# STM32_microcontroller_power.net
KiCad netlist of a schematic drawn in Altium Designer
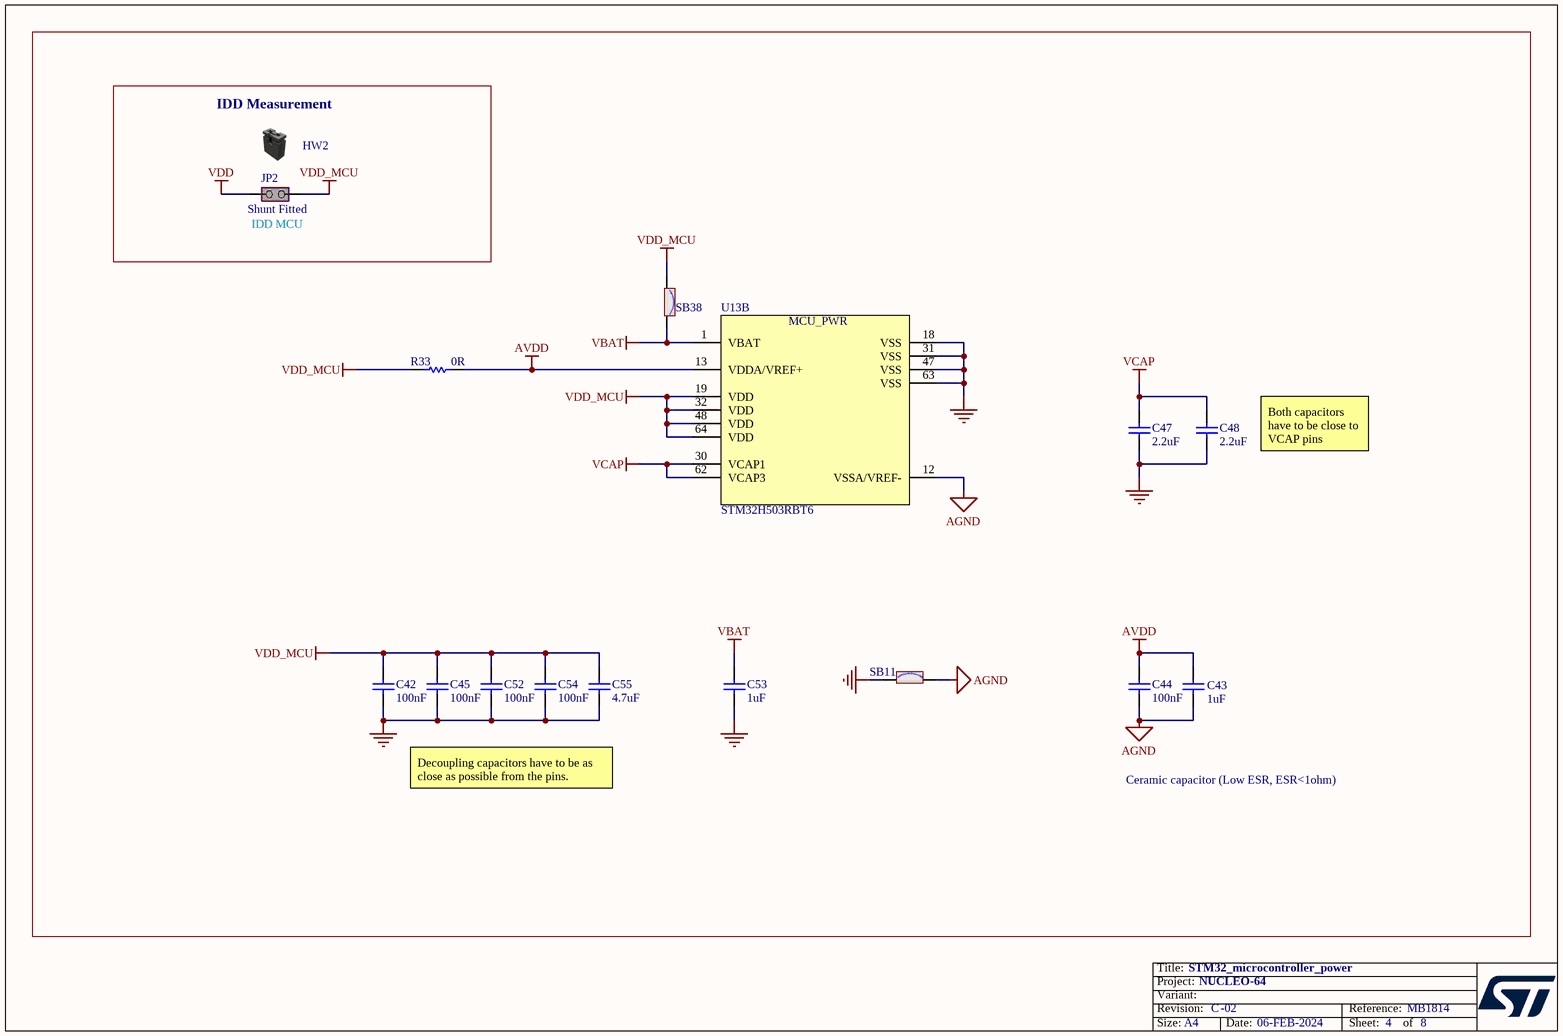
[diagram p0: STM32_microcontroller_power.SchDoc]

(export (version "E")
  (design (tool "Eeschema 10.0.6"))
  (components
    (comp (ref "C42")
      (value "100nF")
      (footprint "C0402")
      (description "Capacitor, MLCC, 100nF, 16V, X7R, +/-10%, 0402, T=0.5mm")
      (fields (field (name "INTERNAL_PART_NUMBER") "MCD-00006") (field (name "MANUFACTURER") "YAGEO"))
      (libsource (lib "MCD_PARTS_database") (part "Capacitor"))
    )
    (comp (ref "C43")
      (value "1uF")
      (footprint "C0603")
      (description "Capacitor, MLCC, 1uF, 16V, X5R, 10%, 0603, T=0,8mm")
      (fields
        (field (name "INTERNAL_PART_NUMBER") "MCD-00010")
        (field (name "MANUFACTURER_PART_NUMBER") "CC0603KRX5R7BB105")
        (field (name "PROVIDED_BY") "Subcon")
      )
      (libsource (lib "MCD_PARTS_database") (part "Capacitor"))
    )
    (comp (ref "C44")
      (value "100nF")
      (footprint "C0402")
      (description "Capacitor, MLCC, 100nF, 16V, X7R, +/-10%, 0402, T=0.5mm")
      (fields (field (name "INTERNAL_PART_NUMBER") "MCD-00006") (field (name "MANUFACTURER") "YAGEO"))
      (libsource (lib "MCD_PARTS_database") (part "Capacitor"))
    )
    (comp (ref "C45")
      (value "100nF")
      (footprint "C0402")
      (description "Capacitor, MLCC, 100nF, 16V, X7R, +/-10%, 0402, T=0.5mm")
      (fields (field (name "INTERNAL_PART_NUMBER") "MCD-00006") (field (name "MANUFACTURER") "YAGEO"))
      (libsource (lib "MCD_PARTS_database") (part "Capacitor"))
    )
    (comp (ref "C47")
      (value "2.2uF")
      (footprint "C0603")
      (description "Capacitor, MLCC, 2.2uF, 10V, X5R, +/- 10%, 0603, T=0,8mm")
      (fields (field (name "INTERNAL_PART_NUMBER") "MCD-00012") (field (name "BMS_PART_NUMBER") "9142010"))
      (libsource (lib "MCD_PARTS_database") (part "Capacitor"))
    )
    (comp (ref "C48")
      (value "2.2uF")
      (footprint "C0603")
      (description "Capacitor, MLCC, 2.2uF, 10V, X5R, +/- 10%, 0603, T=0,8mm")
      (fields (field (name "INTERNAL_PART_NUMBER") "MCD-00012") (field (name "BMS_PART_NUMBER") "9142010"))
      (libsource (lib "MCD_PARTS_database") (part "Capacitor"))
    )
    (comp (ref "C52")
      (value "100nF")
      (footprint "C0402")
      (description "Capacitor, MLCC, 100nF, 16V, X7R, +/-10%, 0402, T=0.5mm")
      (fields (field (name "INTERNAL_PART_NUMBER") "MCD-00006") (field (name "MANUFACTURER") "YAGEO"))
      (libsource (lib "MCD_PARTS_database") (part "Capacitor"))
    )
    (comp (ref "C53")
      (value "1uF")
      (footprint "C0603")
      (description "Capacitor, MLCC, 1uF, 16V, X5R, 10%, 0603, T=0,8mm")
      (fields
        (field (name "INTERNAL_PART_NUMBER") "MCD-00010")
        (field (name "MANUFACTURER_PART_NUMBER") "CC0603KRX5R7BB105")
        (field (name "PROVIDED_BY") "Subcon")
      )
      (libsource (lib "MCD_PARTS_database") (part "Capacitor"))
    )
    (comp (ref "C54")
      (value "100nF")
      (footprint "C0402")
      (description "Capacitor, MLCC, 100nF, 16V, X7R, +/-10%, 0402, T=0.5mm")
      (fields (field (name "INTERNAL_PART_NUMBER") "MCD-00006") (field (name "MANUFACTURER") "YAGEO"))
      (libsource (lib "MCD_PARTS_database") (part "Capacitor"))
    )
    (comp (ref "C55")
      (value "4.7uF")
      (footprint "C0603")
      (description "Capacitor, MLCC, 4.7uF, 16V, X5R, 10%, 0603, T=0.8mm")
      (fields
        (field (name "INTERNAL_PART_NUMBER") "MCD-00009")
        (field (name "MANUFACTURER_PART_NUMBER") "CC0603KRX5R7BB475")
        (field (name "PROVIDED_BY") "subcon")
      )
      (libsource (lib "MCD_PARTS_database") (part "Capacitor"))
    )
    (comp (ref "HW2")
      (value "~")
      (description "SHUNT 2.54mm BLACK")
      (fields
        (field (name "INTERNAL_PART_NUMBER") "MCD-00043")
        (field (name "MANUFACTURER_PART_NUMBER") "SNT-100-BK-G")
        (field (name "PROVIDED_BY") "Subcon")
      )
      (libsource (lib "MCD_PARTS_database") (part "Shunt Black 2.54mm"))
    )
    (comp (ref "JP2")
      (value "Shunt Fitted")
      (footprint "CON_SAMTEC_TSW-102-07-G-S")
      (description "Header, 2x1, 2,54mm, VR, TH, Height 5.84mm/2.54mm - Shunt Fitted by default")
      (fields
        (field (name "INTERNAL_PART_NUMBER") "MCD-00683")
        (field (name "MANUFACTURER_PART_NUMBER") "TSW-102-07-x-S")
        (field (name "PROVIDED_BY") "Subcon")
      )
      (libsource (lib "MCD_PARTS_database") (part "Jumper_Header 2x1 Fitted"))
    )
    (comp (ref "R33")
      (value "0R")
      (footprint "R0603")
      (description "Resistor, 0R, 0603, +/-5%, 1/10W")
      (fields (field (name "INTERNAL_PART_NUMBER") "MCD-00056") (field (name "MANUFACTURER") "YAGEO"))
      (libsource (lib "MCD_PARTS_database") (part "Resistor"))
    )
    (comp (ref "SB11")
      (value "~")
      (footprint "SOLDER-BRIDGE_R0603-0R")
      (description "Solder Bridge ON")
      (fields
        (field (name "INTERNAL_PART_NUMBER") "MCD-00071")
        (field (name "MANUFACTURER_PART_NUMBER") "RC0603JR-070RL")
        (field (name "PROVIDED_BY") "SUBCO")
      )
      (libsource (lib "") (part "SB_ON_1"))
    )
    (comp (ref "SB38")
      (value "~")
      (footprint "SOLDER-BRIDGE_R0603-0R")
      (description "Solder Bridge ON")
      (fields
        (field (name "INTERNAL_PART_NUMBER") "MCD-00071")
        (field (name "MANUFACTURER_PART_NUMBER") "RC0603JR-070RL")
        (field (name "PROVIDED_BY") "SUBCO")
      )
      (libsource (lib "MCD_PARTS_database") (part "SB_ON"))
    )
    (comp (ref "U13")
      (value "STM32H503RBT6")
      (footprint "ICC_LQFP64_10X10_P050_SOCKET_YAMAICHI_IC149-064-069-B5_NM")
      (description "MCU, Arm Cortex-M33, 250MHz, 32-bit MCU, 128KB flash, 32KB SRAM")
      (fields
        (field (name "INTERNAL_PART_NUMBER") "MCD-02438")
        (field (name "MANUFACTURER") "STMICROELECTRONICS")
      )
      (libsource (lib "MCD_PARTS_database") (part "STM32H503RBH6"))
    )
  )
  (nets
    (net (code "1") (name "AGND") (class "Default")
      (node (ref "C43") (pin "1") (pinfunction "1_1") (pintype "passive"))
      (node (ref "C44") (pin "1") (pinfunction "1_1") (pintype "passive"))
      (node (ref "SB11") (pin "2") (pinfunction "2_2") (pintype "passive"))
      (node (ref "U13") (pin "12") (pinfunction "VSSA/VREF-_12") (pintype "passive"))
    )
    (net (code "2") (name "AVDD") (class "Default")
      (node (ref "C43") (pin "2") (pinfunction "2_2") (pintype "passive"))
      (node (ref "C44") (pin "2") (pinfunction "2_2") (pintype "passive"))
      (node (ref "R33") (pin "2") (pinfunction "2_2") (pintype "passive"))
      (node (ref "U13") (pin "13") (pinfunction "VDDA/VREF+_13") (pintype "passive"))
    )
    (net (code "3") (name "GND") (class "Default")
      (node (ref "C42") (pin "1") (pinfunction "1_1") (pintype "passive"))
      (node (ref "C45") (pin "1") (pinfunction "1_1") (pintype "passive"))
      (node (ref "C47") (pin "1") (pinfunction "1_1") (pintype "passive"))
      (node (ref "C48") (pin "1") (pinfunction "1_1") (pintype "passive"))
      (node (ref "C52") (pin "1") (pinfunction "1_1") (pintype "passive"))
      (node (ref "C53") (pin "1") (pinfunction "1_1") (pintype "passive"))
      (node (ref "C54") (pin "1") (pinfunction "1_1") (pintype "passive"))
      (node (ref "C55") (pin "1") (pinfunction "1_1") (pintype "passive"))
      (node (ref "SB11") (pin "1") (pinfunction "1_1") (pintype "passive"))
      (node (ref "U13") (pin "18") (pinfunction "VSS_18") (pintype "passive"))
      (node (ref "U13") (pin "31") (pinfunction "VSS_31") (pintype "passive"))
      (node (ref "U13") (pin "47") (pinfunction "VSS_47") (pintype "passive"))
      (node (ref "U13") (pin "63") (pinfunction "VSS_63") (pintype "passive"))
    )
    (net (code "4") (name "VBAT") (class "Default")
      (node (ref "C53") (pin "2") (pinfunction "2_2") (pintype "passive"))
      (node (ref "SB38") (pin "2") (pinfunction "2_2") (pintype "passive"))
      (node (ref "U13") (pin "1") (pinfunction "VBAT_1") (pintype "passive"))
    )
    (net (code "5") (name "VCAP") (class "Default")
      (node (ref "C47") (pin "2") (pinfunction "2_2") (pintype "passive"))
      (node (ref "C48") (pin "2") (pinfunction "2_2") (pintype "passive"))
      (node (ref "U13") (pin "30") (pinfunction "VCAP1_30") (pintype "passive"))
      (node (ref "U13") (pin "62") (pinfunction "VCAP3_62") (pintype "passive"))
    )
    (net (code "6") (name "VDD") (class "Default")
      (node (ref "JP2") (pin "1") (pinfunction "COMMON_1") (pintype "passive"))
    )
    (net (code "7") (name "VDD_MCU") (class "Default")
      (node (ref "C42") (pin "2") (pinfunction "2_2") (pintype "passive"))
      (node (ref "C45") (pin "2") (pinfunction "2_2") (pintype "passive"))
      (node (ref "C52") (pin "2") (pinfunction "2_2") (pintype "passive"))
      (node (ref "C54") (pin "2") (pinfunction "2_2") (pintype "passive"))
      (node (ref "C55") (pin "2") (pinfunction "2_2") (pintype "passive"))
      (node (ref "JP2") (pin "2") (pinfunction "NO_2") (pintype "passive"))
      (node (ref "R33") (pin "1") (pinfunction "1_1") (pintype "passive"))
      (node (ref "SB38") (pin "1") (pinfunction "1_1") (pintype "passive"))
      (node (ref "U13") (pin "19") (pinfunction "VDD_19") (pintype "passive"))
      (node (ref "U13") (pin "32") (pinfunction "VDD_32") (pintype "passive"))
      (node (ref "U13") (pin "48") (pinfunction "VDD_48") (pintype "passive"))
      (node (ref "U13") (pin "64") (pinfunction "VDD_64") (pintype "passive"))
    )
  )
)
